# DownConverter.net
KiCad netlist of a schematic drawn in Altium Designer
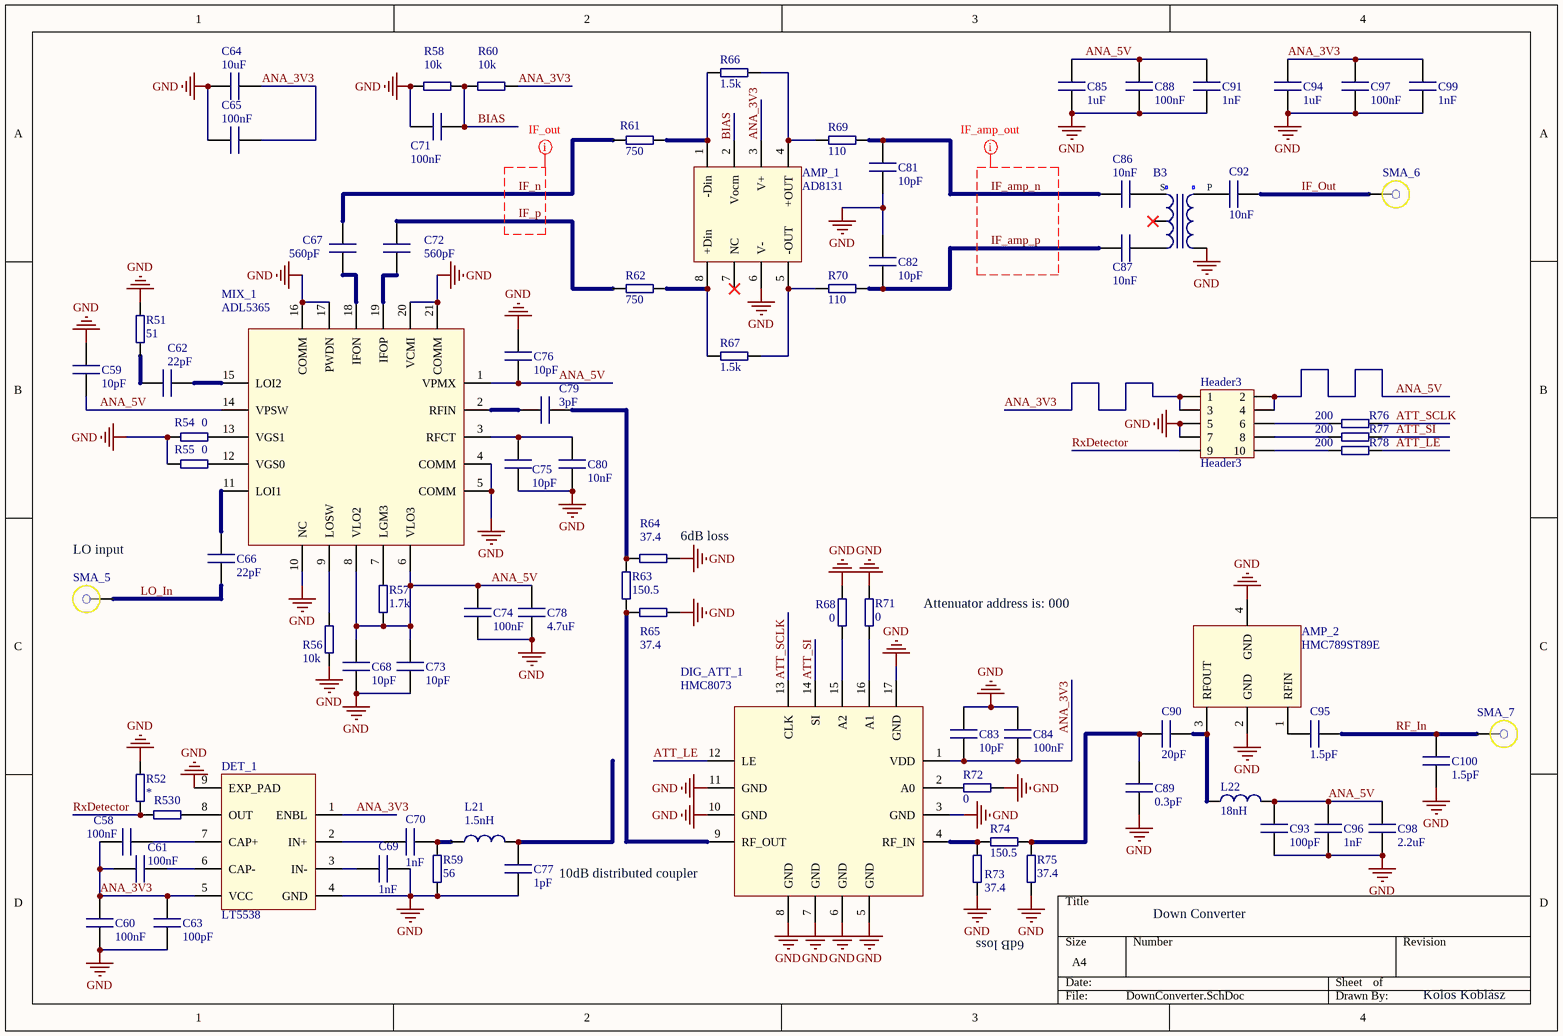
[diagram p0: DownConverter.SchDoc]

(export (version "E")
  (design (tool "Eeschema 10.0.6"))
  (components
    (comp (ref "AMP_1")
      (value "AD8131")
      (description "High Speed Differential Driver")
      (fields (field (name "MANUFACTURER") "Analog Devices"))
      (libsource (lib "RadioProjectSchLib") (part "AD8131"))
    )
    (comp (ref "AMP_2")
      (value "HMC789ST89E")
      (description "Gain Block MMIC")
      (fields (field (name "MANUFACTURER") "Analog Devices"))
      (libsource (lib "RadioProjectSchLib") (part "HMC789ST89E"))
    )
    (comp (ref "B3")
      (value "Balun")
      (footprint "Balun_Coil")
      (description "SMD Balun")
      (libsource (lib "RadioProjectSchLib") (part "Balun1"))
    )
    (comp (ref "C58")
      (value "100nF")
      (footprint "0805 SMD Passive")
      (description "SMD Capacitor")
      (fields (field (name "Comment") "Cap1"))
      (libsource (lib "RadioProjectSchLib") (part "Cap1"))
    )
    (comp (ref "C59")
      (value "10pF")
      (footprint "0805 SMD Passive")
      (description "SMD Capacitor")
      (fields (field (name "Comment") "Cap1"))
      (libsource (lib "RadioProjectSchLib") (part "Cap1"))
    )
    (comp (ref "C60")
      (value "100nF")
      (footprint "0805 SMD Passive")
      (description "SMD Capacitor")
      (fields (field (name "Comment") "Cap1"))
      (libsource (lib "RadioProjectSchLib") (part "Cap1"))
    )
    (comp (ref "C61")
      (value "100nF")
      (footprint "0805 SMD Passive")
      (description "SMD Capacitor")
      (fields (field (name "Comment") "Cap1"))
      (libsource (lib "RadioProjectSchLib") (part "Cap1"))
    )
    (comp (ref "C62")
      (value "22pF")
      (footprint "0805 SMD Passive")
      (description "SMD Capacitor")
      (fields (field (name "Comment") "Cap1"))
      (libsource (lib "RadioProjectSchLib") (part "Cap1"))
    )
    (comp (ref "C63")
      (value "100pF")
      (footprint "0805 SMD Passive")
      (description "SMD Capacitor")
      (fields (field (name "Comment") "Cap1"))
      (libsource (lib "RadioProjectSchLib") (part "Cap1"))
    )
    (comp (ref "C64")
      (value "10uF")
      (footprint "0805 SMD Passive")
      (description "SMD Capacitor")
      (fields (field (name "Comment") "Cap1"))
      (libsource (lib "RadioProjectSchLib") (part "Cap1"))
    )
    (comp (ref "C65")
      (value "100nF")
      (footprint "0805 SMD Passive")
      (description "SMD Capacitor")
      (fields (field (name "Comment") "Cap1"))
      (libsource (lib "RadioProjectSchLib") (part "Cap1"))
    )
    (comp (ref "C66")
      (value "22pF")
      (footprint "0805 SMD Passive")
      (description "SMD Capacitor")
      (fields (field (name "Comment") "Cap1"))
      (libsource (lib "RadioProjectSchLib") (part "Cap1"))
    )
    (comp (ref "C67")
      (value "560pF")
      (footprint "0805 SMD Passive")
      (description "SMD Capacitor")
      (fields (field (name "Comment") "Cap1"))
      (libsource (lib "RadioProjectSchLib") (part "Cap1"))
    )
    (comp (ref "C68")
      (value "10pF")
      (footprint "0805 SMD Passive")
      (description "SMD Capacitor")
      (fields (field (name "Comment") "Cap1"))
      (libsource (lib "RadioProjectSchLib") (part "Cap1"))
    )
    (comp (ref "C69")
      (value "1nF")
      (footprint "0805 SMD Passive")
      (description "SMD Capacitor")
      (fields (field (name "Comment") "Cap1"))
      (libsource (lib "RadioProjectSchLib") (part "Cap1"))
    )
    (comp (ref "C70")
      (value "1nF")
      (footprint "0805 SMD Passive")
      (description "SMD Capacitor")
      (fields (field (name "Comment") "Cap1"))
      (libsource (lib "RadioProjectSchLib") (part "Cap1"))
    )
    (comp (ref "C71")
      (value "100nF")
      (footprint "0805 SMD Passive")
      (description "SMD Capacitor")
      (fields (field (name "Comment") "Cap1"))
      (libsource (lib "RadioProjectSchLib") (part "Cap1"))
    )
    (comp (ref "C72")
      (value "560pF")
      (footprint "0805 SMD Passive")
      (description "SMD Capacitor")
      (fields (field (name "Comment") "Cap1"))
      (libsource (lib "RadioProjectSchLib") (part "Cap1"))
    )
    (comp (ref "C73")
      (value "10pF")
      (footprint "0805 SMD Passive")
      (description "SMD Capacitor")
      (fields (field (name "Comment") "Cap1"))
      (libsource (lib "RadioProjectSchLib") (part "Cap1"))
    )
    (comp (ref "C74")
      (value "100nF")
      (footprint "0805 SMD Passive")
      (description "SMD Capacitor")
      (fields (field (name "Comment") "Cap1"))
      (libsource (lib "RadioProjectSchLib") (part "Cap1"))
    )
    (comp (ref "C75")
      (value "10pF")
      (footprint "0805 SMD Passive")
      (description "SMD Capacitor")
      (fields (field (name "Comment") "Cap1"))
      (libsource (lib "RadioProjectSchLib") (part "Cap1"))
    )
    (comp (ref "C76")
      (value "10pF")
      (footprint "0805 SMD Passive")
      (description "SMD Capacitor")
      (fields (field (name "Comment") "Cap1"))
      (libsource (lib "RadioProjectSchLib") (part "Cap1"))
    )
    (comp (ref "C77")
      (value "1pF")
      (footprint "0805 SMD Passive")
      (description "SMD Capacitor")
      (fields (field (name "Comment") "Cap1"))
      (libsource (lib "RadioProjectSchLib") (part "Cap1"))
    )
    (comp (ref "C78")
      (value "4.7uF")
      (footprint "0805 SMD Passive")
      (description "SMD Capacitor")
      (fields (field (name "Comment") "Cap1"))
      (libsource (lib "RadioProjectSchLib") (part "Cap1"))
    )
    (comp (ref "C79")
      (value "3pF")
      (footprint "0805 SMD Passive")
      (description "SMD Capacitor")
      (fields (field (name "Comment") "Cap1"))
      (libsource (lib "RadioProjectSchLib") (part "Cap1"))
    )
    (comp (ref "C80")
      (value "10nF")
      (footprint "0805 SMD Passive")
      (description "SMD Capacitor")
      (fields (field (name "Comment") "Cap1"))
      (libsource (lib "RadioProjectSchLib") (part "Cap1"))
    )
    (comp (ref "C81")
      (value "10pF")
      (footprint "0805 SMD Passive")
      (description "SMD Capacitor")
      (fields (field (name "Comment") "Cap1"))
      (libsource (lib "RadioProjectSchLib") (part "Cap1"))
    )
    (comp (ref "C82")
      (value "10pF")
      (footprint "0805 SMD Passive")
      (description "SMD Capacitor")
      (fields (field (name "Comment") "Cap1"))
      (libsource (lib "RadioProjectSchLib") (part "Cap1"))
    )
    (comp (ref "C83")
      (value "10pF")
      (footprint "0805 SMD Passive")
      (description "SMD Capacitor")
      (fields (field (name "Comment") "Cap1"))
      (libsource (lib "RadioProjectSchLib") (part "Cap1"))
    )
    (comp (ref "C84")
      (value "100nF")
      (footprint "0805 SMD Passive")
      (description "SMD Capacitor")
      (fields (field (name "Comment") "Cap1"))
      (libsource (lib "RadioProjectSchLib") (part "Cap1"))
    )
    (comp (ref "C85")
      (value "1uF")
      (footprint "0805 SMD Passive")
      (description "SMD Capacitor")
      (fields (field (name "Comment") "Cap1"))
      (libsource (lib "RadioProjectSchLib") (part "Cap1"))
    )
    (comp (ref "C86")
      (value "10nF")
      (footprint "0805 SMD Passive")
      (description "SMD Capacitor")
      (fields (field (name "Comment") "Cap1"))
      (libsource (lib "RadioProjectSchLib") (part "Cap1"))
    )
    (comp (ref "C87")
      (value "10nF")
      (footprint "0805 SMD Passive")
      (description "SMD Capacitor")
      (fields (field (name "Comment") "Cap1"))
      (libsource (lib "RadioProjectSchLib") (part "Cap1"))
    )
    (comp (ref "C88")
      (value "100nF")
      (footprint "0805 SMD Passive")
      (description "SMD Capacitor")
      (fields (field (name "Comment") "Cap1"))
      (libsource (lib "RadioProjectSchLib") (part "Cap1"))
    )
    (comp (ref "C89")
      (value "0.3pF")
      (footprint "0805 SMD Passive")
      (description "SMD Capacitor")
      (fields (field (name "Comment") "Cap1"))
      (libsource (lib "RadioProjectSchLib") (part "Cap1"))
    )
    (comp (ref "C90")
      (value "20pF")
      (footprint "0805 SMD Passive")
      (description "SMD Capacitor")
      (fields (field (name "Comment") "Cap1"))
      (libsource (lib "RadioProjectSchLib") (part "Cap1"))
    )
    (comp (ref "C91")
      (value "1nF")
      (footprint "0805 SMD Passive")
      (description "SMD Capacitor")
      (fields (field (name "Comment") "Cap1"))
      (libsource (lib "RadioProjectSchLib") (part "Cap1"))
    )
    (comp (ref "C92")
      (value "10nF")
      (footprint "0805 SMD Passive")
      (description "SMD Capacitor")
      (fields (field (name "Comment") "Cap1"))
      (libsource (lib "RadioProjectSchLib") (part "Cap1"))
    )
    (comp (ref "C93")
      (value "100pF")
      (footprint "0805 SMD Passive")
      (description "SMD Capacitor")
      (fields (field (name "Comment") "Cap1"))
      (libsource (lib "RadioProjectSchLib") (part "Cap1"))
    )
    (comp (ref "C94")
      (value "1uF")
      (footprint "0805 SMD Passive")
      (description "SMD Capacitor")
      (fields (field (name "Comment") "Cap1"))
      (libsource (lib "RadioProjectSchLib") (part "Cap1"))
    )
    (comp (ref "C95")
      (value "1.5pF")
      (footprint "0805 SMD Passive")
      (description "SMD Capacitor")
      (fields (field (name "Comment") "Cap1"))
      (libsource (lib "RadioProjectSchLib") (part "Cap1"))
    )
    (comp (ref "C96")
      (value "1nF")
      (footprint "0805 SMD Passive")
      (description "SMD Capacitor")
      (fields (field (name "Comment") "Cap1"))
      (libsource (lib "RadioProjectSchLib") (part "Cap1"))
    )
    (comp (ref "C97")
      (value "100nF")
      (footprint "0805 SMD Passive")
      (description "SMD Capacitor")
      (fields (field (name "Comment") "Cap1"))
      (libsource (lib "RadioProjectSchLib") (part "Cap1"))
    )
    (comp (ref "C98")
      (value "2.2uF")
      (footprint "0805 SMD Passive")
      (description "SMD Capacitor")
      (fields (field (name "Comment") "Cap1"))
      (libsource (lib "RadioProjectSchLib") (part "Cap1"))
    )
    (comp (ref "C99")
      (value "1nF")
      (footprint "0805 SMD Passive")
      (description "SMD Capacitor")
      (fields (field (name "Comment") "Cap1"))
      (libsource (lib "RadioProjectSchLib") (part "Cap1"))
    )
    (comp (ref "C100")
      (value "1.5pF")
      (footprint "0805 SMD Passive")
      (description "SMD Capacitor")
      (fields (field (name "Comment") "Cap1"))
      (libsource (lib "RadioProjectSchLib") (part "Cap1"))
    )
    (comp (ref "DET_1")
      (value "LT5538")
      (description "Detector")
      (fields (field (name "MANUFACTURER") "Analog Devices"))
      (libsource (lib "RadioProjectSchLib") (part "LT5538"))
    )
    (comp (ref "DIG_ATT_1")
      (value "HMC8073")
      (description "Digital Attenuator")
      (fields (field (name "MANUFACTURER") "Analog Devices"))
      (libsource (lib "RadioProjectSchLib") (part "HMC8073"))
    )
    (comp (ref "Header3")
      (value "Header3")
      (footprint "Header3")
      (description "10 pin DIL header")
      (libsource (lib "RadioProjectSchLib") (part "Header3"))
    )
    (comp (ref "L21")
      (value "1.5nH")
      (footprint "0805 SMD Passive")
      (description "SMD Inductor")
      (fields (field (name "Comment") "Inductor"))
      (libsource (lib "RadioProjectSchLib") (part "Ind1"))
    )
    (comp (ref "L22")
      (value "18nH")
      (footprint "0805 SMD Passive")
      (description "SMD Inductor")
      (fields (field (name "Comment") "Inductor"))
      (libsource (lib "") (part "Ind1_1"))
    )
    (comp (ref "MIX_1")
      (value "ADL5365")
      (description "RF Mixer")
      (fields (field (name "MANUFACTURER") "Analog Devices"))
      (libsource (lib "RadioProjectSchLib") (part "ADL5365"))
    )
    (comp (ref "R51")
      (value "51")
      (footprint "0805 SMD Passive")
      (description "SMD Resistor")
      (fields (field (name "Comment") "Resistor"))
      (libsource (lib "RadioProjectSchLib") (part "Res1"))
    )
    (comp (ref "R52")
      (value "Resistor")
      (footprint "0805 SMD Passive")
      (description "SMD Resistor")
      (fields (field (name "ALTIUM_VALUE") "*"))
      (libsource (lib "RadioProjectSchLib") (part "Res1"))
    )
    (comp (ref "R53")
      (value "0")
      (footprint "0805 SMD Passive")
      (description "SMD Resistor")
      (fields (field (name "Comment") "Resistor"))
      (libsource (lib "RadioProjectSchLib") (part "Res1"))
    )
    (comp (ref "R54")
      (value "0")
      (footprint "0805 SMD Passive")
      (description "SMD Resistor")
      (fields (field (name "Comment") "Resistor"))
      (libsource (lib "RadioProjectSchLib") (part "Res1"))
    )
    (comp (ref "R55")
      (value "0")
      (footprint "0805 SMD Passive")
      (description "SMD Resistor")
      (fields (field (name "Comment") "Resistor"))
      (libsource (lib "RadioProjectSchLib") (part "Res1"))
    )
    (comp (ref "R56")
      (value "10k")
      (footprint "0805 SMD Passive")
      (description "SMD Resistor")
      (fields (field (name "Comment") "Resistor"))
      (libsource (lib "RadioProjectSchLib") (part "Res1"))
    )
    (comp (ref "R57")
      (value "1.7k")
      (footprint "0805 SMD Passive")
      (description "SMD Resistor")
      (fields (field (name "Comment") "Resistor"))
      (libsource (lib "RadioProjectSchLib") (part "Res1"))
    )
    (comp (ref "R58")
      (value "10k")
      (footprint "0805 SMD Passive")
      (description "SMD Resistor")
      (fields (field (name "Comment") "Resistor"))
      (libsource (lib "RadioProjectSchLib") (part "Res1"))
    )
    (comp (ref "R59")
      (value "56")
      (footprint "0805 SMD Passive")
      (description "SMD Resistor")
      (fields (field (name "Comment") "Resistor"))
      (libsource (lib "RadioProjectSchLib") (part "Res1"))
    )
    (comp (ref "R60")
      (value "10k")
      (footprint "0805 SMD Passive")
      (description "SMD Resistor")
      (fields (field (name "Comment") "Resistor"))
      (libsource (lib "RadioProjectSchLib") (part "Res1"))
    )
    (comp (ref "R61")
      (value "750")
      (footprint "0805 SMD Passive")
      (description "SMD Resistor")
      (fields (field (name "Comment") "Resistor"))
      (libsource (lib "RadioProjectSchLib") (part "Res1"))
    )
    (comp (ref "R62")
      (value "750")
      (footprint "0805 SMD Passive")
      (description "SMD Resistor")
      (fields (field (name "Comment") "Resistor"))
      (libsource (lib "RadioProjectSchLib") (part "Res1"))
    )
    (comp (ref "R63")
      (value "150.5")
      (footprint "0805 SMD Passive")
      (description "SMD Resistor")
      (fields (field (name "Comment") "Resistor"))
      (libsource (lib "RadioProjectSchLib") (part "Res1"))
    )
    (comp (ref "R64")
      (value "37.4")
      (footprint "0805 SMD Passive")
      (description "SMD Resistor")
      (fields (field (name "Comment") "Resistor"))
      (libsource (lib "RadioProjectSchLib") (part "Res1"))
    )
    (comp (ref "R65")
      (value "37.4")
      (footprint "0805 SMD Passive")
      (description "SMD Resistor")
      (fields (field (name "Comment") "Resistor"))
      (libsource (lib "RadioProjectSchLib") (part "Res1"))
    )
    (comp (ref "R66")
      (value "1.5k")
      (footprint "0805 SMD Passive")
      (description "SMD Resistor")
      (fields (field (name "Comment") "Resistor"))
      (libsource (lib "RadioProjectSchLib") (part "Res1"))
    )
    (comp (ref "R67")
      (value "1.5k")
      (footprint "0805 SMD Passive")
      (description "SMD Resistor")
      (fields (field (name "Comment") "Resistor"))
      (libsource (lib "RadioProjectSchLib") (part "Res1"))
    )
    (comp (ref "R68")
      (value "0")
      (footprint "0805 SMD Passive")
      (description "SMD Resistor")
      (fields (field (name "Comment") "Resistor"))
      (libsource (lib "RadioProjectSchLib") (part "Res1"))
    )
    (comp (ref "R69")
      (value "110")
      (footprint "0805 SMD Passive")
      (description "SMD Resistor")
      (fields (field (name "Comment") "Resistor"))
      (libsource (lib "RadioProjectSchLib") (part "Res1"))
    )
    (comp (ref "R70")
      (value "110")
      (footprint "0805 SMD Passive")
      (description "SMD Resistor")
      (fields (field (name "Comment") "Resistor"))
      (libsource (lib "RadioProjectSchLib") (part "Res1"))
    )
    (comp (ref "R71")
      (value "0")
      (footprint "0805 SMD Passive")
      (description "SMD Resistor")
      (fields (field (name "Comment") "Resistor"))
      (libsource (lib "RadioProjectSchLib") (part "Res1"))
    )
    (comp (ref "R72")
      (value "0")
      (footprint "0805 SMD Passive")
      (description "SMD Resistor")
      (fields (field (name "Comment") "Resistor"))
      (libsource (lib "RadioProjectSchLib") (part "Res1"))
    )
    (comp (ref "R73")
      (value "37.4")
      (footprint "0805 SMD Passive")
      (description "SMD Resistor")
      (fields (field (name "Comment") "Resistor"))
      (libsource (lib "RadioProjectSchLib") (part "Res1"))
    )
    (comp (ref "R74")
      (value "150.5")
      (footprint "0805 SMD Passive")
      (description "SMD Resistor")
      (fields (field (name "Comment") "Resistor"))
      (libsource (lib "RadioProjectSchLib") (part "Res1"))
    )
    (comp (ref "R75")
      (value "37.4")
      (footprint "0805 SMD Passive")
      (description "SMD Resistor")
      (fields (field (name "Comment") "Resistor"))
      (libsource (lib "RadioProjectSchLib") (part "Res1"))
    )
    (comp (ref "R76")
      (value "200")
      (footprint "0805 SMD Passive")
      (description "SMD Resistor")
      (fields (field (name "Comment") "Resistor"))
      (libsource (lib "RadioProjectSchLib") (part "Res1"))
    )
    (comp (ref "R77")
      (value "200")
      (footprint "0805 SMD Passive")
      (description "SMD Resistor")
      (fields (field (name "Comment") "Resistor"))
      (libsource (lib "RadioProjectSchLib") (part "Res1"))
    )
    (comp (ref "R78")
      (value "200")
      (footprint "0805 SMD Passive")
      (description "SMD Resistor")
      (fields (field (name "Comment") "Resistor"))
      (libsource (lib "RadioProjectSchLib") (part "Res1"))
    )
    (comp (ref "SMA_5")
      (value "SMA1")
      (footprint "SMA Flange")
      (description "SMA Female")
      (libsource (lib "RadioProjectSchLib") (part "SMA1"))
    )
    (comp (ref "SMA_6")
      (value "SMA1")
      (footprint "SMA Flange")
      (description "SMA Female")
      (libsource (lib "RadioProjectSchLib") (part "SMA1"))
    )
    (comp (ref "SMA_7")
      (value "SMA1")
      (footprint "SMA Flange")
      (description "SMA Female")
      (libsource (lib "RadioProjectSchLib") (part "SMA1"))
    )
  )
  (nets
    (net (code "1") (name "/ANA_3V3") (class "Default")
      (node (ref "AMP_1") (pin "3") (pinfunction "V+_3") (pintype "passive"))
      (node (ref "C58") (pin "2") (pinfunction "*_2") (pintype "passive"))
      (node (ref "C60") (pin "1") (pinfunction "*_1") (pintype "passive"))
      (node (ref "C61") (pin "2") (pinfunction "*_2") (pintype "passive"))
      (node (ref "C63") (pin "1") (pinfunction "*_1") (pintype "passive"))
      (node (ref "C64") (pin "1") (pinfunction "*_1") (pintype "passive"))
      (node (ref "C65") (pin "2") (pinfunction "*_2") (pintype "passive"))
      (node (ref "C83") (pin "1") (pinfunction "*_1") (pintype "passive"))
      (node (ref "C84") (pin "1") (pinfunction "*_1") (pintype "passive"))
      (node (ref "C94") (pin "2") (pinfunction "*_2") (pintype "passive"))
      (node (ref "C97") (pin "2") (pinfunction "*_2") (pintype "passive"))
      (node (ref "C99") (pin "2") (pinfunction "*_2") (pintype "passive"))
      (node (ref "DET_1") (pin "1") (pinfunction "ENBL_1") (pintype "passive"))
      (node (ref "DET_1") (pin "5") (pinfunction "VCC_5") (pintype "passive"))
      (node (ref "DIG_ATT_1") (pin "1") (pinfunction "VDD_1") (pintype "passive"))
      (node (ref "Header3") (pin "1") (pinfunction "1_1") (pintype "passive"))
      (node (ref "Header3") (pin "3") (pinfunction "3_3") (pintype "passive"))
      (node (ref "R60") (pin "2") (pinfunction "*_2") (pintype "passive"))
    )
    (net (code "2") (name "/ANA_5V") (class "Default")
      (node (ref "C59") (pin "2") (pinfunction "*_2") (pintype "passive"))
      (node (ref "C68") (pin "2") (pinfunction "*_2") (pintype "passive"))
      (node (ref "C73") (pin "2") (pinfunction "*_2") (pintype "passive"))
      (node (ref "C74") (pin "2") (pinfunction "*_2") (pintype "passive"))
      (node (ref "C76") (pin "2") (pinfunction "*_2") (pintype "passive"))
      (node (ref "C78") (pin "2") (pinfunction "*_2") (pintype "passive"))
      (node (ref "C85") (pin "2") (pinfunction "*_2") (pintype "passive"))
      (node (ref "C88") (pin "2") (pinfunction "*_2") (pintype "passive"))
      (node (ref "C91") (pin "2") (pinfunction "*_2") (pintype "passive"))
      (node (ref "C93") (pin "1") (pinfunction "*_1") (pintype "passive"))
      (node (ref "C96") (pin "1") (pinfunction "*_1") (pintype "passive"))
      (node (ref "C98") (pin "1") (pinfunction "*_1") (pintype "passive"))
      (node (ref "Header3") (pin "2") (pinfunction "2_2") (pintype "passive"))
      (node (ref "Header3") (pin "4") (pinfunction "4_4") (pintype "passive"))
      (node (ref "L22") (pin "2") (pinfunction "*_2") (pintype "passive"))
      (node (ref "MIX_1") (pin "1") (pinfunction "VPMX_1") (pintype "passive"))
      (node (ref "MIX_1") (pin "14") (pinfunction "VPSW_14") (pintype "passive"))
      (node (ref "MIX_1") (pin "6") (pinfunction "VLO3_6") (pintype "passive"))
      (node (ref "MIX_1") (pin "8") (pinfunction "VLO2_8") (pintype "passive"))
      (node (ref "R57") (pin "1") (pinfunction "*_1") (pintype "passive"))
    )
    (net (code "3") (name "/ATT_LE") (class "Default")
      (node (ref "DIG_ATT_1") (pin "12") (pinfunction "LE_12") (pintype "passive"))
      (node (ref "R78") (pin "1") (pinfunction "*_1") (pintype "passive"))
    )
    (net (code "4") (name "/ATT_SCLK") (class "Default")
      (node (ref "DIG_ATT_1") (pin "13") (pinfunction "CLK_13") (pintype "passive"))
      (node (ref "R76") (pin "1") (pinfunction "*_1") (pintype "passive"))
    )
    (net (code "5") (name "/ATT_SI") (class "Default")
      (node (ref "DIG_ATT_1") (pin "14") (pinfunction "SI_14") (pintype "passive"))
      (node (ref "R77") (pin "1") (pinfunction "*_1") (pintype "passive"))
    )
    (net (code "6") (name "/BIAS") (class "Default")
      (node (ref "AMP_1") (pin "2") (pinfunction "Vocm_2") (pintype "passive"))
      (node (ref "C71") (pin "1") (pinfunction "*_1") (pintype "passive"))
      (node (ref "R58") (pin "2") (pinfunction "*_2") (pintype "passive"))
      (node (ref "R60") (pin "1") (pinfunction "*_1") (pintype "passive"))
    )
    (net (code "7") (name "/IF_Out") (class "Default")
      (node (ref "C92") (pin "1") (pinfunction "*_1") (pintype "passive"))
      (node (ref "SMA_6") (pin "1") (pinfunction "1_1") (pintype "passive"))
    )
    (net (code "8") (name "/IF_amp_n") (class "Default")
      (node (ref "C81") (pin "2") (pinfunction "*_2") (pintype "passive"))
      (node (ref "C86") (pin "2") (pinfunction "*_2") (pintype "passive"))
      (node (ref "R69") (pin "2") (pinfunction "*_2") (pintype "passive"))
    )
    (net (code "9") (name "/IF_amp_p") (class "Default")
      (node (ref "C82") (pin "1") (pinfunction "*_1") (pintype "passive"))
      (node (ref "C87") (pin "2") (pinfunction "*_2") (pintype "passive"))
      (node (ref "R70") (pin "2") (pinfunction "*_2") (pintype "passive"))
    )
    (net (code "10") (name "/IF_n") (class "Default")
      (node (ref "C67") (pin "1") (pinfunction "*_1") (pintype "passive"))
      (node (ref "R61") (pin "1") (pinfunction "*_1") (pintype "passive"))
    )
    (net (code "11") (name "/IF_p") (class "Default")
      (node (ref "C72") (pin "1") (pinfunction "*_1") (pintype "passive"))
      (node (ref "R62") (pin "1") (pinfunction "*_1") (pintype "passive"))
    )
    (net (code "12") (name "/LO_In") (class "Default")
      (node (ref "C66") (pin "1") (pinfunction "*_1") (pintype "passive"))
      (node (ref "SMA_5") (pin "1") (pinfunction "1_1") (pintype "passive"))
    )
    (net (code "13") (name "/RF_In") (class "Default")
      (node (ref "C100") (pin "2") (pinfunction "*_2") (pintype "passive"))
      (node (ref "C95") (pin "1") (pinfunction "*_1") (pintype "passive"))
      (node (ref "SMA_7") (pin "1") (pinfunction "1_1") (pintype "passive"))
    )
    (net (code "14") (name "/RxDetector") (class "Default")
      (node (ref "Header3") (pin "9") (pinfunction "9_9") (pintype "passive"))
      (node (ref "R52") (pin "1") (pinfunction "*_1") (pintype "passive"))
      (node (ref "R53") (pin "1") (pinfunction "*_1") (pintype "passive"))
    )
    (net (code "15") (name "GND") (class "Default")
      (node (ref "AMP_1") (pin "6") (pinfunction "V-_6") (pintype "passive"))
      (node (ref "AMP_2") (pin "2") (pinfunction "GND_2") (pintype "passive"))
      (node (ref "AMP_2") (pin "4") (pinfunction "GND_4") (pintype "passive"))
      (node (ref "B3") (pin "4") (pinfunction "4_4") (pintype "passive"))
      (node (ref "C100") (pin "1") (pinfunction "*_1") (pintype "passive"))
      (node (ref "C59") (pin "1") (pinfunction "*_1") (pintype "passive"))
      (node (ref "C60") (pin "2") (pinfunction "*_2") (pintype "passive"))
      (node (ref "C63") (pin "2") (pinfunction "*_2") (pintype "passive"))
      (node (ref "C64") (pin "2") (pinfunction "*_2") (pintype "passive"))
      (node (ref "C65") (pin "1") (pinfunction "*_1") (pintype "passive"))
      (node (ref "C68") (pin "1") (pinfunction "*_1") (pintype "passive"))
      (node (ref "C69") (pin "1") (pinfunction "*_1") (pintype "passive"))
      (node (ref "C71") (pin "2") (pinfunction "*_2") (pintype "passive"))
      (node (ref "C73") (pin "1") (pinfunction "*_1") (pintype "passive"))
      (node (ref "C74") (pin "1") (pinfunction "*_1") (pintype "passive"))
      (node (ref "C75") (pin "1") (pinfunction "*_1") (pintype "passive"))
      (node (ref "C76") (pin "1") (pinfunction "*_1") (pintype "passive"))
      (node (ref "C77") (pin "1") (pinfunction "*_1") (pintype "passive"))
      (node (ref "C78") (pin "1") (pinfunction "*_1") (pintype "passive"))
      (node (ref "C80") (pin "1") (pinfunction "*_1") (pintype "passive"))
      (node (ref "C81") (pin "1") (pinfunction "*_1") (pintype "passive"))
      (node (ref "C82") (pin "2") (pinfunction "*_2") (pintype "passive"))
      (node (ref "C83") (pin "2") (pinfunction "*_2") (pintype "passive"))
      (node (ref "C84") (pin "2") (pinfunction "*_2") (pintype "passive"))
      (node (ref "C85") (pin "1") (pinfunction "*_1") (pintype "passive"))
      (node (ref "C88") (pin "1") (pinfunction "*_1") (pintype "passive"))
      (node (ref "C89") (pin "2") (pinfunction "*_2") (pintype "passive"))
      (node (ref "C91") (pin "1") (pinfunction "*_1") (pintype "passive"))
      (node (ref "C93") (pin "2") (pinfunction "*_2") (pintype "passive"))
      (node (ref "C94") (pin "1") (pinfunction "*_1") (pintype "passive"))
      (node (ref "C96") (pin "2") (pinfunction "*_2") (pintype "passive"))
      (node (ref "C97") (pin "1") (pinfunction "*_1") (pintype "passive"))
      (node (ref "C98") (pin "2") (pinfunction "*_2") (pintype "passive"))
      (node (ref "C99") (pin "1") (pinfunction "*_1") (pintype "passive"))
      (node (ref "DET_1") (pin "4") (pinfunction "GND_4") (pintype "passive"))
      (node (ref "DET_1") (pin "9") (pinfunction "EXP_PAD_9") (pintype "passive"))
      (node (ref "DIG_ATT_1") (pin "10") (pinfunction "GND_10") (pintype "passive"))
      (node (ref "DIG_ATT_1") (pin "11") (pinfunction "GND_11") (pintype "passive"))
      (node (ref "DIG_ATT_1") (pin "17") (pinfunction "GND_17") (pintype "passive"))
      (node (ref "DIG_ATT_1") (pin "3") (pinfunction "GND_3") (pintype "passive"))
      (node (ref "DIG_ATT_1") (pin "5") (pinfunction "GND_5") (pintype "passive"))
      (node (ref "DIG_ATT_1") (pin "6") (pinfunction "GND_6") (pintype "passive"))
      (node (ref "DIG_ATT_1") (pin "7") (pinfunction "GND_7") (pintype "passive"))
      (node (ref "DIG_ATT_1") (pin "8") (pinfunction "GND_8") (pintype "passive"))
      (node (ref "Header3") (pin "5") (pinfunction "5_5") (pintype "passive"))
      (node (ref "Header3") (pin "7") (pinfunction "7_7") (pintype "passive"))
      (node (ref "MIX_1") (pin "10") (pinfunction "NC_10") (pintype "passive"))
      (node (ref "MIX_1") (pin "16") (pinfunction "COMM_16") (pintype "passive"))
      (node (ref "MIX_1") (pin "17") (pinfunction "PWDN_17") (pintype "passive"))
      (node (ref "MIX_1") (pin "20") (pinfunction "VCMI_20") (pintype "passive"))
      (node (ref "MIX_1") (pin "21") (pinfunction "COMM_21") (pintype "passive"))
      (node (ref "MIX_1") (pin "4") (pinfunction "COMM_4") (pintype "passive"))
      (node (ref "MIX_1") (pin "5") (pinfunction "COMM_5") (pintype "passive"))
      (node (ref "R51") (pin "1") (pinfunction "*_1") (pintype "passive"))
      (node (ref "R52") (pin "2") (pinfunction "*_2") (pintype "passive"))
      (node (ref "R54") (pin "2") (pinfunction "*_2") (pintype "passive"))
      (node (ref "R55") (pin "2") (pinfunction "*_2") (pintype "passive"))
      (node (ref "R56") (pin "1") (pinfunction "*_1") (pintype "passive"))
      (node (ref "R58") (pin "1") (pinfunction "*_1") (pintype "passive"))
      (node (ref "R59") (pin "1") (pinfunction "*_1") (pintype "passive"))
      (node (ref "R64") (pin "2") (pinfunction "*_2") (pintype "passive"))
      (node (ref "R65") (pin "2") (pinfunction "*_2") (pintype "passive"))
      (node (ref "R68") (pin "2") (pinfunction "*_2") (pintype "passive"))
      (node (ref "R71") (pin "2") (pinfunction "*_2") (pintype "passive"))
      (node (ref "R72") (pin "2") (pinfunction "*_2") (pintype "passive"))
      (node (ref "R73") (pin "2") (pinfunction "*_2") (pintype "passive"))
      (node (ref "R75") (pin "2") (pinfunction "*_2") (pintype "passive"))
    )
    (net (code "16") (name "Net-(AMP_1-+Din)") (class "Default")
      (node (ref "AMP_1") (pin "8") (pinfunction "+Din_8") (pintype "passive"))
      (node (ref "R62") (pin "2") (pinfunction "*_2") (pintype "passive"))
      (node (ref "R67") (pin "1") (pinfunction "*_1") (pintype "passive"))
    )
    (net (code "17") (name "Net-(AMP_1-+OUT)") (class "Default")
      (node (ref "AMP_1") (pin "4") (pinfunction "+OUT_4") (pintype "passive"))
      (node (ref "R66") (pin "2") (pinfunction "*_2") (pintype "passive"))
      (node (ref "R69") (pin "1") (pinfunction "*_1") (pintype "passive"))
    )
    (net (code "18") (name "Net-(AMP_1--Din)") (class "Default")
      (node (ref "AMP_1") (pin "1") (pinfunction "-Din_1") (pintype "passive"))
      (node (ref "R61") (pin "2") (pinfunction "*_2") (pintype "passive"))
      (node (ref "R66") (pin "1") (pinfunction "*_1") (pintype "passive"))
    )
    (net (code "19") (name "Net-(AMP_1--OUT)") (class "Default")
      (node (ref "AMP_1") (pin "5") (pinfunction "-OUT_5") (pintype "passive"))
      (node (ref "R67") (pin "2") (pinfunction "*_2") (pintype "passive"))
      (node (ref "R70") (pin "1") (pinfunction "*_1") (pintype "passive"))
    )
    (net (code "20") (name "Net-(AMP_2-RFIN)") (class "Default")
      (node (ref "AMP_2") (pin "1") (pinfunction "RFIN_1") (pintype "passive"))
      (node (ref "C95") (pin "2") (pinfunction "*_2") (pintype "passive"))
    )
    (net (code "21") (name "Net-(AMP_2-RFOUT)") (class "Default")
      (node (ref "AMP_2") (pin "3") (pinfunction "RFOUT_3") (pintype "passive"))
      (node (ref "C90") (pin "1") (pinfunction "*_1") (pintype "passive"))
      (node (ref "L22") (pin "1") (pinfunction "*_1") (pintype "passive"))
    )
    (net (code "22") (name "Net-(B3-Pad1)") (class "Default")
      (node (ref "B3") (pin "1") (pinfunction "1_1") (pintype "passive"))
      (node (ref "C86") (pin "1") (pinfunction "*_1") (pintype "passive"))
    )
    (net (code "23") (name "Net-(B3-Pad3)") (class "Default")
      (node (ref "B3") (pin "3") (pinfunction "3_3") (pintype "passive"))
      (node (ref "C87") (pin "1") (pinfunction "*_1") (pintype "passive"))
    )
    (net (code "24") (name "Net-(B3-Pad5)") (class "Default")
      (node (ref "B3") (pin "5") (pinfunction "5_5") (pintype "passive"))
      (node (ref "C92") (pin "2") (pinfunction "*_2") (pintype "passive"))
    )
    (net (code "25") (name "Net-(C62-*-Pad1)") (class "Default")
      (node (ref "C62") (pin "1") (pinfunction "*_1") (pintype "passive"))
      (node (ref "R51") (pin "2") (pinfunction "*_2") (pintype "passive"))
    )
    (net (code "26") (name "Net-(C70-*-Pad1)") (class "Default")
      (node (ref "C70") (pin "1") (pinfunction "*_1") (pintype "passive"))
      (node (ref "L21") (pin "2") (pinfunction "*_2") (pintype "passive"))
      (node (ref "R59") (pin "2") (pinfunction "*_2") (pintype "passive"))
    )
    (net (code "27") (name "Net-(C77-*-Pad2)") (class "Default")
      (node (ref "C77") (pin "2") (pinfunction "*_2") (pintype "passive"))
      (node (ref "L21") (pin "1") (pinfunction "*_1") (pintype "passive"))
    )
    (net (code "28") (name "Net-(C79-*-Pad1)") (class "Default")
      (node (ref "C79") (pin "1") (pinfunction "*_1") (pintype "passive"))
      (node (ref "R63") (pin "1") (pinfunction "*_1") (pintype "passive"))
      (node (ref "R64") (pin "1") (pinfunction "*_1") (pintype "passive"))
    )
    (net (code "29") (name "Net-(C89-*-Pad1)") (class "Default")
      (node (ref "C89") (pin "1") (pinfunction "*_1") (pintype "passive"))
      (node (ref "C90") (pin "2") (pinfunction "*_2") (pintype "passive"))
      (node (ref "R74") (pin "1") (pinfunction "*_1") (pintype "passive"))
      (node (ref "R75") (pin "1") (pinfunction "*_1") (pintype "passive"))
    )
    (net (code "30") (name "Net-(DET_1-CAP+)") (class "Default")
      (node (ref "C58") (pin "1") (pinfunction "*_1") (pintype "passive"))
      (node (ref "DET_1") (pin "7") (pinfunction "CAP+_7") (pintype "passive"))
    )
    (net (code "31") (name "Net-(DET_1-CAP-)") (class "Default")
      (node (ref "C61") (pin "1") (pinfunction "*_1") (pintype "passive"))
      (node (ref "DET_1") (pin "6") (pinfunction "CAP-_6") (pintype "passive"))
    )
    (net (code "32") (name "Net-(DET_1-IN+)") (class "Default")
      (node (ref "C70") (pin "2") (pinfunction "*_2") (pintype "passive"))
      (node (ref "DET_1") (pin "2") (pinfunction "IN+_2") (pintype "passive"))
    )
    (net (code "33") (name "Net-(DET_1-IN-)") (class "Default")
      (node (ref "C69") (pin "2") (pinfunction "*_2") (pintype "passive"))
      (node (ref "DET_1") (pin "3") (pinfunction "IN-_3") (pintype "passive"))
    )
    (net (code "34") (name "Net-(DET_1-OUT)") (class "Default")
      (node (ref "DET_1") (pin "8") (pinfunction "OUT_8") (pintype "passive"))
      (node (ref "R53") (pin "2") (pinfunction "*_2") (pintype "passive"))
    )
    (net (code "35") (name "Net-(DIG_ATT_1-A0)") (class "Default")
      (node (ref "DIG_ATT_1") (pin "2") (pinfunction "A0_2") (pintype "passive"))
      (node (ref "R72") (pin "1") (pinfunction "*_1") (pintype "passive"))
    )
    (net (code "36") (name "Net-(DIG_ATT_1-A1)") (class "Default")
      (node (ref "DIG_ATT_1") (pin "16") (pinfunction "A1_16") (pintype "passive"))
      (node (ref "R71") (pin "1") (pinfunction "*_1") (pintype "passive"))
    )
    (net (code "37") (name "Net-(DIG_ATT_1-A2)") (class "Default")
      (node (ref "DIG_ATT_1") (pin "15") (pinfunction "A2_15") (pintype "passive"))
      (node (ref "R68") (pin "1") (pinfunction "*_1") (pintype "passive"))
    )
    (net (code "38") (name "Net-(DIG_ATT_1-RF_IN)") (class "Default")
      (node (ref "DIG_ATT_1") (pin "4") (pinfunction "RF_IN_4") (pintype "passive"))
      (node (ref "R73") (pin "1") (pinfunction "*_1") (pintype "passive"))
      (node (ref "R74") (pin "2") (pinfunction "*_2") (pintype "passive"))
    )
    (net (code "39") (name "Net-(DIG_ATT_1-RF_OUT)") (class "Default")
      (node (ref "DIG_ATT_1") (pin "9") (pinfunction "RF_OUT_9") (pintype "passive"))
      (node (ref "R63") (pin "2") (pinfunction "*_2") (pintype "passive"))
      (node (ref "R65") (pin "1") (pinfunction "*_1") (pintype "passive"))
    )
    (net (code "40") (name "Net-(Header3-Pad6)") (class "Default")
      (node (ref "Header3") (pin "6") (pinfunction "6_6") (pintype "passive"))
      (node (ref "R76") (pin "2") (pinfunction "*_2") (pintype "passive"))
    )
    (net (code "41") (name "Net-(Header3-Pad8)") (class "Default")
      (node (ref "Header3") (pin "8") (pinfunction "8_8") (pintype "passive"))
      (node (ref "R77") (pin "2") (pinfunction "*_2") (pintype "passive"))
    )
    (net (code "42") (name "Net-(Header3-Pad10)") (class "Default")
      (node (ref "Header3") (pin "10") (pinfunction "10_10") (pintype "passive"))
      (node (ref "R78") (pin "2") (pinfunction "*_2") (pintype "passive"))
    )
    (net (code "43") (name "Net-(MIX_1-IFON)") (class "Default")
      (node (ref "C67") (pin "2") (pinfunction "*_2") (pintype "passive"))
      (node (ref "MIX_1") (pin "18") (pinfunction "IFON_18") (pintype "passive"))
    )
    (net (code "44") (name "Net-(MIX_1-IFOP)") (class "Default")
      (node (ref "C72") (pin "2") (pinfunction "*_2") (pintype "passive"))
      (node (ref "MIX_1") (pin "19") (pinfunction "IFOP_19") (pintype "passive"))
    )
    (net (code "45") (name "Net-(MIX_1-LGM3)") (class "Default")
      (node (ref "MIX_1") (pin "7") (pinfunction "LGM3_7") (pintype "passive"))
      (node (ref "R57") (pin "2") (pinfunction "*_2") (pintype "passive"))
    )
    (net (code "46") (name "Net-(MIX_1-LOI1)") (class "Default")
      (node (ref "C66") (pin "2") (pinfunction "*_2") (pintype "passive"))
      (node (ref "MIX_1") (pin "11") (pinfunction "LOI1_11") (pintype "passive"))
    )
    (net (code "47") (name "Net-(MIX_1-LOI2)") (class "Default")
      (node (ref "C62") (pin "2") (pinfunction "*_2") (pintype "passive"))
      (node (ref "MIX_1") (pin "15") (pinfunction "LOI2_15") (pintype "passive"))
    )
    (net (code "48") (name "Net-(MIX_1-LOSW)") (class "Default")
      (node (ref "MIX_1") (pin "9") (pinfunction "LOSW_9") (pintype "passive"))
      (node (ref "R56") (pin "2") (pinfunction "*_2") (pintype "passive"))
    )
    (net (code "49") (name "Net-(MIX_1-RFCT)") (class "Default")
      (node (ref "C75") (pin "2") (pinfunction "*_2") (pintype "passive"))
      (node (ref "C80") (pin "2") (pinfunction "*_2") (pintype "passive"))
      (node (ref "MIX_1") (pin "3") (pinfunction "RFCT_3") (pintype "passive"))
    )
    (net (code "50") (name "Net-(MIX_1-RFIN)") (class "Default")
      (node (ref "C79") (pin "2") (pinfunction "*_2") (pintype "passive"))
      (node (ref "MIX_1") (pin "2") (pinfunction "RFIN_2") (pintype "passive"))
    )
    (net (code "51") (name "Net-(MIX_1-VGS0)") (class "Default")
      (node (ref "MIX_1") (pin "12") (pinfunction "VGS0_12") (pintype "passive"))
      (node (ref "R55") (pin "1") (pinfunction "*_1") (pintype "passive"))
    )
    (net (code "52") (name "Net-(MIX_1-VGS1)") (class "Default")
      (node (ref "MIX_1") (pin "13") (pinfunction "VGS1_13") (pintype "passive"))
      (node (ref "R54") (pin "1") (pinfunction "*_1") (pintype "passive"))
    )
    (net (code "53") (name "unconnected-(AMP_1-NC-Pad7)") (class "Default")
      (node (ref "AMP_1") (pin "7") (pinfunction "NC_7") (pintype "passive+no_connect"))
    )
    (net (code "54") (name "unconnected-(B3-Pad2)") (class "Default")
      (node (ref "B3") (pin "2") (pinfunction "2_2") (pintype "passive+no_connect"))
    )
  )
)
